# aansluitschema.net
KiCad netlist of a schematic drawn in EAGLE
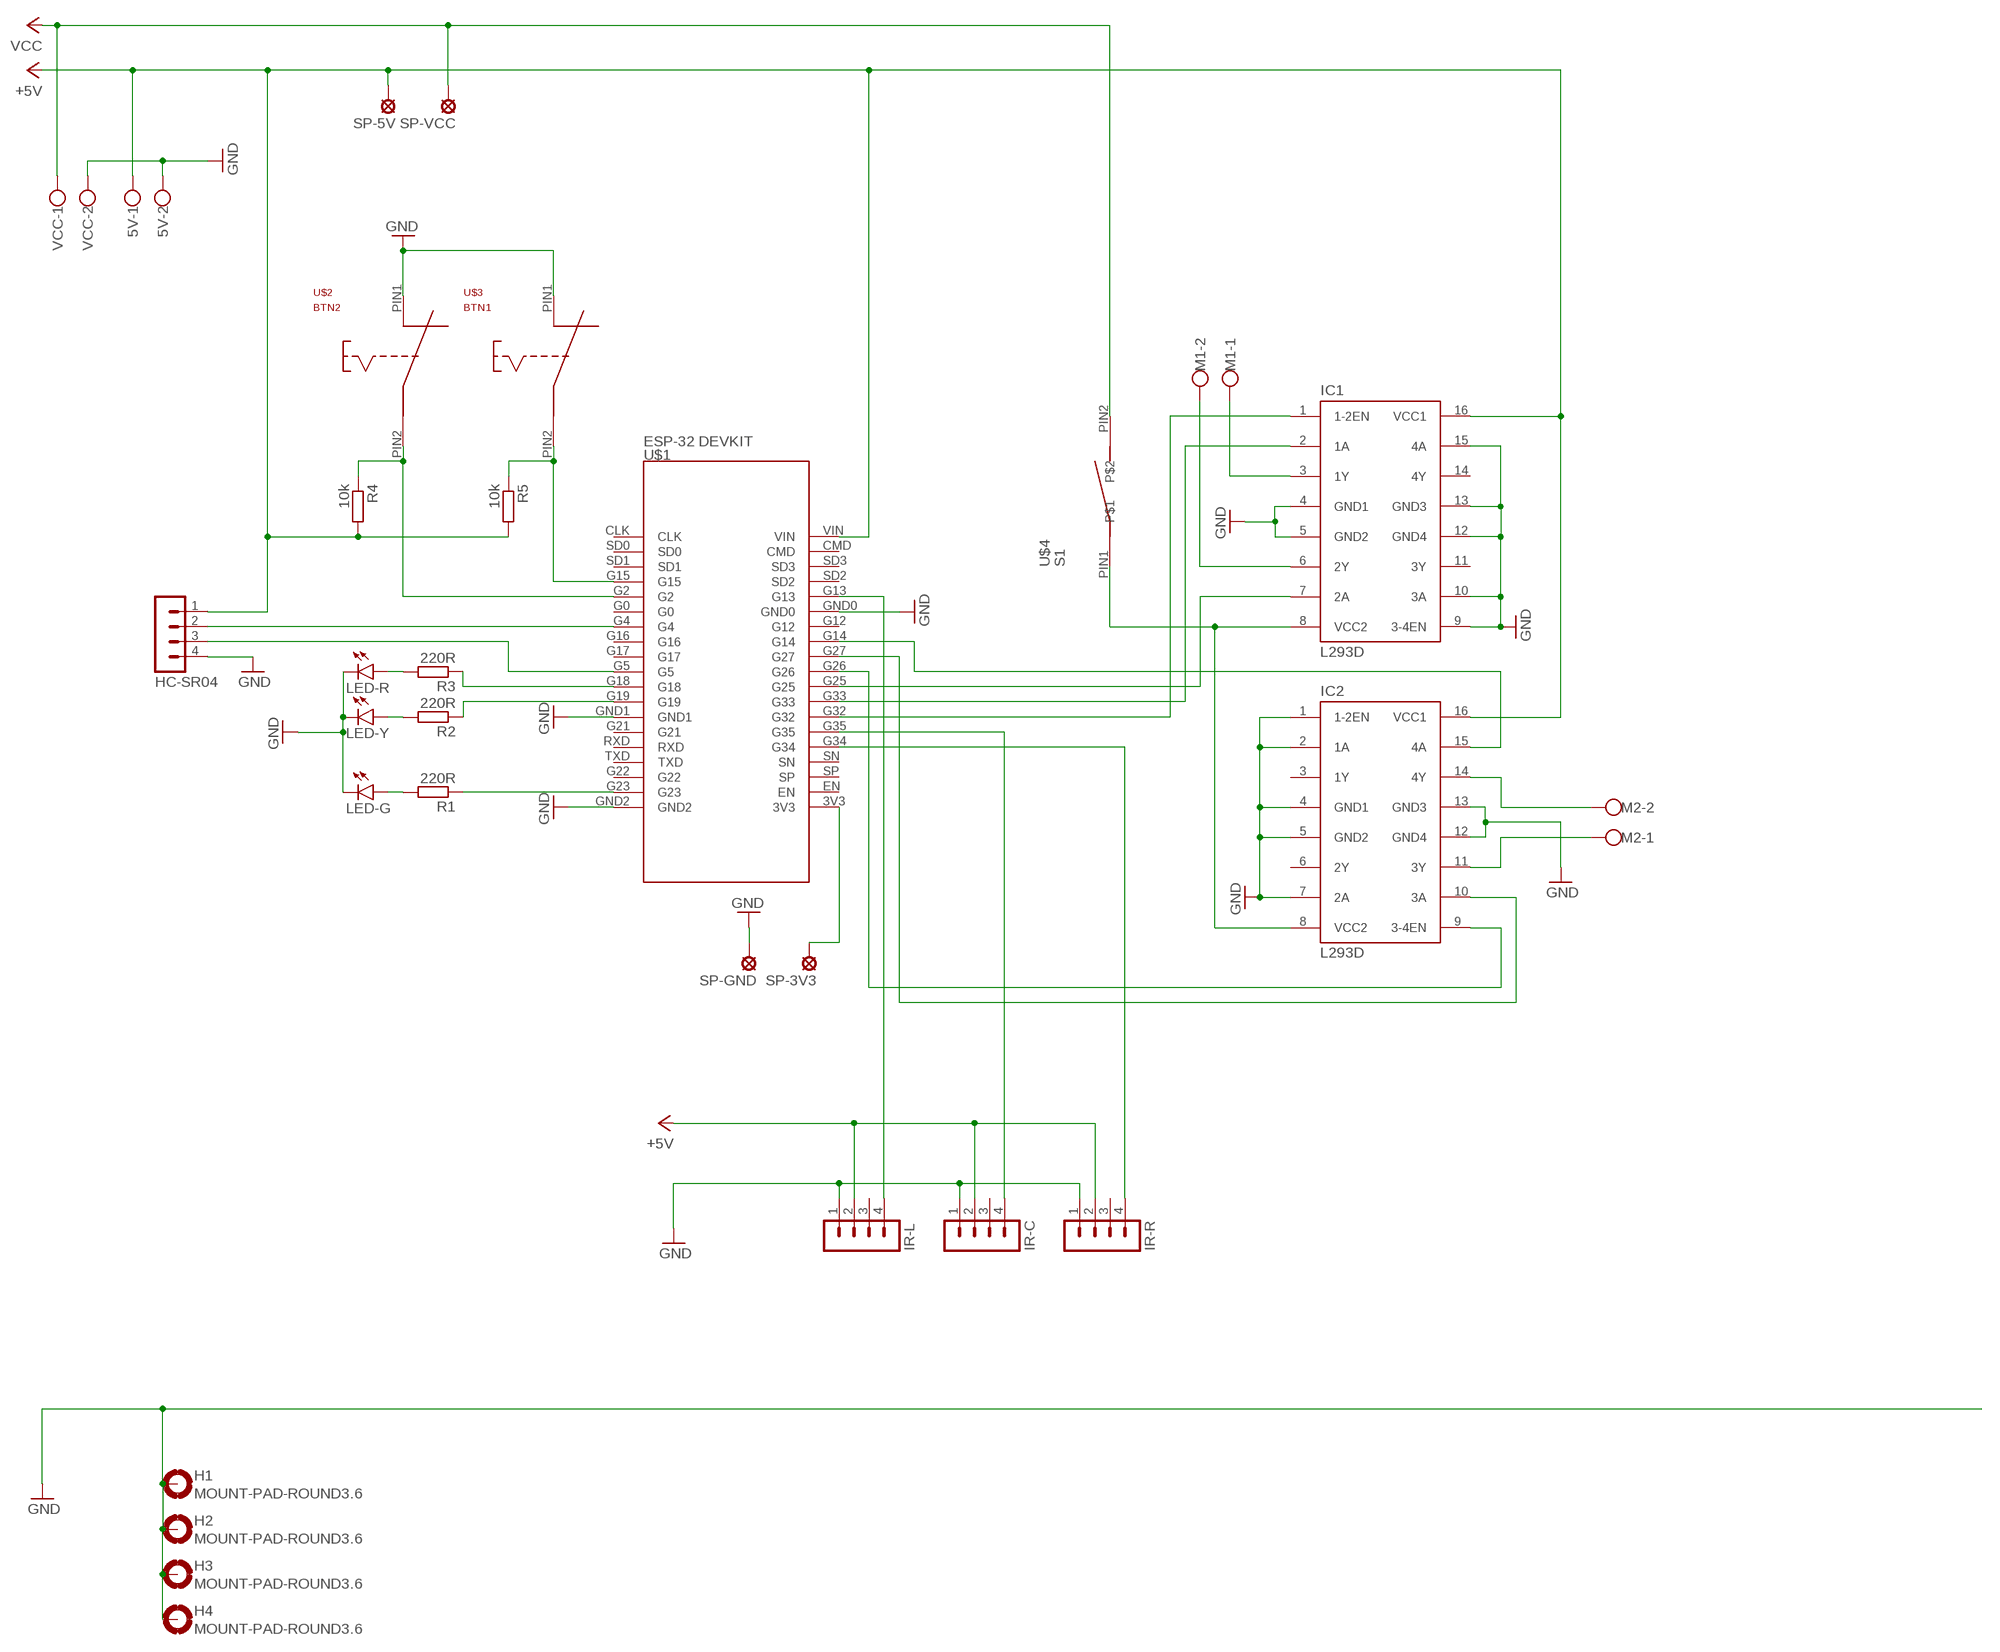
[diagram p0: schematic, sheet 1]

(export (version "E")
  (design (tool "Eeschema 10.0.6"))
  (components
    (comp (ref "5V")
      (value "W237-102")
      (footprint "eagle-import:W237-102")
      (fields (field (name "MPN") "237-102"))
      (libsource (lib "eagle-import") (part "W237-102"))
    )
    (comp (ref "H1")
      (value "MOUNT-PAD-ROUND3.6")
      (footprint "eagle-import:3,6-PAD")
      (libsource (lib "eagle-import") (part "MOUNT-PAD-ROUND3.6"))
    )
    (comp (ref "H2")
      (value "MOUNT-PAD-ROUND3.6")
      (footprint "eagle-import:3,6-PAD")
      (libsource (lib "eagle-import") (part "MOUNT-PAD-ROUND3.6"))
    )
    (comp (ref "H3")
      (value "MOUNT-PAD-ROUND3.6")
      (footprint "eagle-import:3,6-PAD")
      (libsource (lib "eagle-import") (part "MOUNT-PAD-ROUND3.6"))
    )
    (comp (ref "H4")
      (value "MOUNT-PAD-ROUND3.6")
      (footprint "eagle-import:3,6-PAD")
      (libsource (lib "eagle-import") (part "MOUNT-PAD-ROUND3.6"))
    )
    (comp (ref "HC-SR04")
      (value "MA04-1")
      (footprint "eagle-import:MA04-1")
      (libsource (lib "eagle-import") (part "MA04-1"))
    )
    (comp (ref "IC1")
      (value "L293D")
      (footprint "eagle-import:DIL16")
      (fields (field (name "MF") "Arrow Electronics") (field (name "MPN") "L293E"))
      (libsource (lib "eagle-import") (part "L293E"))
    )
    (comp (ref "IC2")
      (value "L293D")
      (footprint "eagle-import:DIL16")
      (fields (field (name "MF") "Arrow Electronics") (field (name "MPN") "L293E"))
      (libsource (lib "eagle-import") (part "L293E"))
    )
    (comp (ref "IR-C")
      (value "MA04-1")
      (footprint "eagle-import:MA04-1")
      (libsource (lib "eagle-import") (part "MA04-1"))
    )
    (comp (ref "IR-L")
      (value "MA04-1")
      (footprint "eagle-import:MA04-1")
      (libsource (lib "eagle-import") (part "MA04-1"))
    )
    (comp (ref "IR-R")
      (value "MA04-1")
      (footprint "eagle-import:MA04-1")
      (libsource (lib "eagle-import") (part "MA04-1"))
    )
    (comp (ref "LED-G")
      (value "LED5MM")
      (footprint "eagle-import:LED5MM")
      (libsource (lib "eagle-import") (part "LED5MM"))
    )
    (comp (ref "LED-R")
      (value "LED5MM")
      (footprint "eagle-import:LED5MM")
      (libsource (lib "eagle-import") (part "LED5MM"))
    )
    (comp (ref "LED-Y")
      (value "LED5MM")
      (footprint "eagle-import:LED5MM")
      (libsource (lib "eagle-import") (part "LED5MM"))
    )
    (comp (ref "M1")
      (value "W237-102")
      (footprint "eagle-import:W237-102")
      (fields (field (name "MPN") "237-102"))
      (libsource (lib "eagle-import") (part "W237-102"))
    )
    (comp (ref "M2")
      (value "W237-102")
      (footprint "eagle-import:W237-102")
      (fields (field (name "MPN") "237-102"))
      (libsource (lib "eagle-import") (part "W237-102"))
    )
    (comp (ref "R1")
      (value "220R")
      (footprint "eagle-import:0207_10")
      (libsource (lib "eagle-import") (part "R-EU_0207/10"))
    )
    (comp (ref "R2")
      (value "220R")
      (footprint "eagle-import:0207_10")
      (libsource (lib "eagle-import") (part "R-EU_0207/10"))
    )
    (comp (ref "R3")
      (value "220R")
      (footprint "eagle-import:0207_10")
      (libsource (lib "eagle-import") (part "R-EU_0207/10"))
    )
    (comp (ref "R4")
      (value "10k")
      (footprint "eagle-import:0207_10")
      (libsource (lib "eagle-import") (part "R-EU_0207/10"))
    )
    (comp (ref "R5")
      (value "10k")
      (footprint "eagle-import:0207_10")
      (libsource (lib "eagle-import") (part "R-EU_0207/10"))
    )
    (comp (ref "SP-3V3")
      (value "LSP10")
      (footprint "eagle-import:LSP10")
      (libsource (lib "eagle-import") (part "LSP10"))
    )
    (comp (ref "SP-5V")
      (value "LSP10")
      (footprint "eagle-import:LSP10")
      (libsource (lib "eagle-import") (part "LSP10"))
    )
    (comp (ref "SP-GND")
      (value "LSP10")
      (footprint "eagle-import:LSP10")
      (libsource (lib "eagle-import") (part "LSP10"))
    )
    (comp (ref "SP-VCC")
      (value "LSP10")
      (footprint "eagle-import:LSP10")
      (libsource (lib "eagle-import") (part "LSP10"))
    )
    (comp (ref "U$1")
      (value "ESP-32 DEVKIT")
      (footprint "eagle-import:ESP-32_DEVKIT")
      (libsource (lib "eagle-import") (part "ESP-32_DEVKIT"))
    )
    (comp (ref "U$2")
      (value "BTN2")
      (footprint "eagle-import:PUSHBUTTON")
      (libsource (lib "eagle-import") (part "PUSHBUTTON"))
    )
    (comp (ref "U$3")
      (value "BTN1")
      (footprint "eagle-import:PUSHBUTTON")
      (libsource (lib "eagle-import") (part "PUSHBUTTON"))
    )
    (comp (ref "U$4")
      (value "S1")
      (footprint "eagle-import:SWITCH")
      (libsource (lib "eagle-import") (part "SWITCH"))
    )
    (comp (ref "VCC")
      (value "W237-102")
      (footprint "eagle-import:W237-102")
      (fields (field (name "MPN") "237-102"))
      (libsource (lib "eagle-import") (part "W237-102"))
    )
  )
  (nets
    (net (code "1") (name "+5V") (class "Default")
      (node (ref "5V") (pin "1") (pinfunction "KL_1") (pintype "passive"))
      (node (ref "HC-SR04") (pin "1") (pinfunction "1_1") (pintype "passive"))
      (node (ref "IC1") (pin "16") (pinfunction "VCC1_16") (pintype "power_in"))
      (node (ref "IC2") (pin "16") (pinfunction "VCC1_16") (pintype "power_in"))
      (node (ref "IR-C") (pin "2") (pinfunction "2_2") (pintype "passive"))
      (node (ref "IR-L") (pin "2") (pinfunction "2_2") (pintype "passive"))
      (node (ref "IR-R") (pin "2") (pinfunction "2_2") (pintype "passive"))
      (node (ref "R4") (pin "2") (pinfunction "2_2") (pintype "passive"))
      (node (ref "R5") (pin "2") (pinfunction "2_2") (pintype "passive"))
      (node (ref "SP-5V") (pin "MP") (pinfunction "MP_MP") (pintype "passive"))
      (node (ref "U$1") (pin "VIN") (pinfunction "VIN_VIN") (pintype "power_in"))
    )
    (net (code "2") (name "GND") (class "Default")
      (node (ref "5V") (pin "2") (pinfunction "KL_2") (pintype "passive"))
      (node (ref "H1") (pin "B3,6") (pinfunction "MOUNT_B3,6") (pintype "passive"))
      (node (ref "H2") (pin "B3,6") (pinfunction "MOUNT_B3,6") (pintype "passive"))
      (node (ref "H3") (pin "B3,6") (pinfunction "MOUNT_B3,6") (pintype "passive"))
      (node (ref "H4") (pin "B3,6") (pinfunction "MOUNT_B3,6") (pintype "passive"))
      (node (ref "HC-SR04") (pin "4") (pinfunction "4_4") (pintype "passive"))
      (node (ref "IC1") (pin "10") (pinfunction "3A_10") (pintype "input"))
      (node (ref "IC1") (pin "12") (pinfunction "GND4_12") (pintype "power_in"))
      (node (ref "IC1") (pin "13") (pinfunction "GND3_13") (pintype "power_in"))
      (node (ref "IC1") (pin "15") (pinfunction "4A_15") (pintype "input"))
      (node (ref "IC1") (pin "4") (pinfunction "GND1_4") (pintype "power_in"))
      (node (ref "IC1") (pin "5") (pinfunction "GND2_5") (pintype "power_in"))
      (node (ref "IC1") (pin "9") (pinfunction "3-4EN_9") (pintype "input"))
      (node (ref "IC2") (pin "1") (pinfunction "1-2EN_1") (pintype "input"))
      (node (ref "IC2") (pin "12") (pinfunction "GND4_12") (pintype "power_in"))
      (node (ref "IC2") (pin "13") (pinfunction "GND3_13") (pintype "power_in"))
      (node (ref "IC2") (pin "2") (pinfunction "1A_2") (pintype "input"))
      (node (ref "IC2") (pin "4") (pinfunction "GND1_4") (pintype "power_in"))
      (node (ref "IC2") (pin "5") (pinfunction "GND2_5") (pintype "power_in"))
      (node (ref "IC2") (pin "7") (pinfunction "2A_7") (pintype "input"))
      (node (ref "IR-C") (pin "1") (pinfunction "1_1") (pintype "passive"))
      (node (ref "IR-L") (pin "1") (pinfunction "1_1") (pintype "passive"))
      (node (ref "IR-R") (pin "1") (pinfunction "1_1") (pintype "passive"))
      (node (ref "LED-G") (pin "K") (pinfunction "C_K") (pintype "passive"))
      (node (ref "LED-R") (pin "K") (pinfunction "C_K") (pintype "passive"))
      (node (ref "LED-Y") (pin "K") (pinfunction "C_K") (pintype "passive"))
      (node (ref "SP-GND") (pin "MP") (pinfunction "MP_MP") (pintype "passive"))
      (node (ref "U$1") (pin "GND0") (pinfunction "GND0_GND0") (pintype "power_in"))
      (node (ref "U$1") (pin "GND1") (pinfunction "GND1_GND1") (pintype "power_in"))
      (node (ref "U$1") (pin "GND2") (pinfunction "GND2_GND2") (pintype "power_in"))
      (node (ref "U$2") (pin "PIN1") (pinfunction "PIN1_PIN1") (pintype "bidirectional"))
      (node (ref "U$3") (pin "PIN1") (pinfunction "PIN1_PIN1") (pintype "bidirectional"))
      (node (ref "VCC") (pin "2") (pinfunction "KL_2") (pintype "passive"))
    )
    (net (code "3") (name "Net-(HC-SR04-Pad2)") (class "Default")
      (node (ref "HC-SR04") (pin "2") (pinfunction "2_2") (pintype "passive"))
      (node (ref "U$1") (pin "G4") (pinfunction "G4_G4") (pintype "bidirectional"))
    )
    (net (code "4") (name "Net-(HC-SR04-Pad3)") (class "Default")
      (node (ref "HC-SR04") (pin "3") (pinfunction "3_3") (pintype "passive"))
      (node (ref "U$1") (pin "G5") (pinfunction "G5_G5") (pintype "bidirectional"))
    )
    (net (code "5") (name "Net-(IC1-1-2EN)") (class "Default")
      (node (ref "IC1") (pin "1") (pinfunction "1-2EN_1") (pintype "input"))
      (node (ref "U$1") (pin "G32") (pinfunction "G32_G32") (pintype "bidirectional"))
    )
    (net (code "6") (name "Net-(IC1-1A)") (class "Default")
      (node (ref "IC1") (pin "2") (pinfunction "1A_2") (pintype "input"))
      (node (ref "U$1") (pin "G33") (pinfunction "G33_G33") (pintype "bidirectional"))
    )
    (net (code "7") (name "Net-(IC1-1Y)") (class "Default")
      (node (ref "IC1") (pin "3") (pinfunction "1Y_3") (pintype "output"))
      (node (ref "M1") (pin "1") (pinfunction "KL_1") (pintype "passive"))
    )
    (net (code "8") (name "Net-(IC1-2A)") (class "Default")
      (node (ref "IC1") (pin "7") (pinfunction "2A_7") (pintype "input"))
      (node (ref "U$1") (pin "G25") (pinfunction "G25_G25") (pintype "bidirectional"))
    )
    (net (code "9") (name "Net-(IC1-2Y)") (class "Default")
      (node (ref "IC1") (pin "6") (pinfunction "2Y_6") (pintype "output"))
      (node (ref "M1") (pin "2") (pinfunction "KL_2") (pintype "passive"))
    )
    (net (code "10") (name "Net-(IC1-VCC2)") (class "Default")
      (node (ref "IC1") (pin "8") (pinfunction "VCC2_8") (pintype "power_in"))
      (node (ref "IC2") (pin "8") (pinfunction "VCC2_8") (pintype "power_in"))
      (node (ref "U$4") (pin "PIN1") (pinfunction "P$1_PIN1") (pintype "bidirectional"))
    )
    (net (code "11") (name "Net-(IC2-3-4EN)") (class "Default")
      (node (ref "IC2") (pin "9") (pinfunction "3-4EN_9") (pintype "input"))
      (node (ref "U$1") (pin "G26") (pinfunction "G26_G26") (pintype "bidirectional"))
    )
    (net (code "12") (name "Net-(IC2-3A)") (class "Default")
      (node (ref "IC2") (pin "10") (pinfunction "3A_10") (pintype "input"))
      (node (ref "U$1") (pin "G27") (pinfunction "G27_G27") (pintype "bidirectional"))
    )
    (net (code "13") (name "Net-(IC2-3Y)") (class "Default")
      (node (ref "IC2") (pin "11") (pinfunction "3Y_11") (pintype "output"))
      (node (ref "M2") (pin "1") (pinfunction "KL_1") (pintype "passive"))
    )
    (net (code "14") (name "Net-(IC2-4A)") (class "Default")
      (node (ref "IC2") (pin "15") (pinfunction "4A_15") (pintype "input"))
      (node (ref "U$1") (pin "G14") (pinfunction "G14_G14") (pintype "bidirectional"))
    )
    (net (code "15") (name "Net-(IC2-4Y)") (class "Default")
      (node (ref "IC2") (pin "14") (pinfunction "4Y_14") (pintype "output"))
      (node (ref "M2") (pin "2") (pinfunction "KL_2") (pintype "passive"))
    )
    (net (code "16") (name "Net-(IR-C-Pad4)") (class "Default")
      (node (ref "IR-C") (pin "4") (pinfunction "4_4") (pintype "passive"))
      (node (ref "U$1") (pin "G35") (pinfunction "G35_G35") (pintype "bidirectional"))
    )
    (net (code "17") (name "Net-(IR-L-Pad4)") (class "Default")
      (node (ref "IR-L") (pin "4") (pinfunction "4_4") (pintype "passive"))
      (node (ref "U$1") (pin "G13") (pinfunction "G13_G13") (pintype "bidirectional"))
    )
    (net (code "18") (name "Net-(IR-R-Pad4)") (class "Default")
      (node (ref "IR-R") (pin "4") (pinfunction "4_4") (pintype "passive"))
      (node (ref "U$1") (pin "G34") (pinfunction "G34_G34") (pintype "bidirectional"))
    )
    (net (code "19") (name "Net-(LED-G-PadA)") (class "Default")
      (node (ref "LED-G") (pin "A") (pinfunction "A_A") (pintype "passive"))
      (node (ref "R1") (pin "2") (pinfunction "2_2") (pintype "passive"))
    )
    (net (code "20") (name "Net-(LED-R-PadA)") (class "Default")
      (node (ref "LED-R") (pin "A") (pinfunction "A_A") (pintype "passive"))
      (node (ref "R3") (pin "2") (pinfunction "2_2") (pintype "passive"))
    )
    (net (code "21") (name "Net-(LED-Y-PadA)") (class "Default")
      (node (ref "LED-Y") (pin "A") (pinfunction "A_A") (pintype "passive"))
      (node (ref "R2") (pin "2") (pinfunction "2_2") (pintype "passive"))
    )
    (net (code "22") (name "Net-(R1-Pad1)") (class "Default")
      (node (ref "R1") (pin "1") (pinfunction "1_1") (pintype "passive"))
      (node (ref "U$1") (pin "G23") (pinfunction "G23_G23") (pintype "bidirectional"))
    )
    (net (code "23") (name "Net-(R2-Pad1)") (class "Default")
      (node (ref "R2") (pin "1") (pinfunction "1_1") (pintype "passive"))
      (node (ref "U$1") (pin "G19") (pinfunction "G19_G19") (pintype "bidirectional"))
    )
    (net (code "24") (name "Net-(R3-Pad1)") (class "Default")
      (node (ref "R3") (pin "1") (pinfunction "1_1") (pintype "passive"))
      (node (ref "U$1") (pin "G18") (pinfunction "G18_G18") (pintype "bidirectional"))
    )
    (net (code "25") (name "Net-(R4-Pad1)") (class "Default")
      (node (ref "R4") (pin "1") (pinfunction "1_1") (pintype "passive"))
      (node (ref "U$1") (pin "G2") (pinfunction "G2_G2") (pintype "bidirectional"))
      (node (ref "U$2") (pin "PIN2") (pinfunction "PIN2_PIN2") (pintype "bidirectional"))
    )
    (net (code "26") (name "Net-(R5-Pad1)") (class "Default")
      (node (ref "R5") (pin "1") (pinfunction "1_1") (pintype "passive"))
      (node (ref "U$1") (pin "G15") (pinfunction "G15_G15") (pintype "bidirectional"))
      (node (ref "U$3") (pin "PIN2") (pinfunction "PIN2_PIN2") (pintype "bidirectional"))
    )
    (net (code "27") (name "Net-(SP-3V3-PadMP)") (class "Default")
      (node (ref "SP-3V3") (pin "MP") (pinfunction "MP_MP") (pintype "passive"))
      (node (ref "U$1") (pin "3V3") (pinfunction "3V3_3V3") (pintype "power_in"))
    )
    (net (code "28") (name "VCC") (class "Default")
      (node (ref "SP-VCC") (pin "MP") (pinfunction "MP_MP") (pintype "passive"))
      (node (ref "U$4") (pin "PIN2") (pinfunction "P$2_PIN2") (pintype "bidirectional"))
      (node (ref "VCC") (pin "1") (pinfunction "KL_1") (pintype "passive"))
    )
    (net (code "29") (name "unconnected-(IC1-3Y-Pad11)") (class "Default")
      (node (ref "IC1") (pin "11") (pinfunction "3Y_11") (pintype "output"))
    )
    (net (code "30") (name "unconnected-(IC1-4Y-Pad14)") (class "Default")
      (node (ref "IC1") (pin "14") (pinfunction "4Y_14") (pintype "output"))
    )
    (net (code "31") (name "unconnected-(IC2-1Y-Pad3)") (class "Default")
      (node (ref "IC2") (pin "3") (pinfunction "1Y_3") (pintype "output"))
    )
    (net (code "32") (name "unconnected-(IC2-2Y-Pad6)") (class "Default")
      (node (ref "IC2") (pin "6") (pinfunction "2Y_6") (pintype "output"))
    )
    (net (code "33") (name "unconnected-(IR-C-Pad3)") (class "Default")
      (node (ref "IR-C") (pin "3") (pinfunction "3_3") (pintype "passive"))
    )
    (net (code "34") (name "unconnected-(IR-L-Pad3)") (class "Default")
      (node (ref "IR-L") (pin "3") (pinfunction "3_3") (pintype "passive"))
    )
    (net (code "35") (name "unconnected-(IR-R-Pad3)") (class "Default")
      (node (ref "IR-R") (pin "3") (pinfunction "3_3") (pintype "passive"))
    )
    (net (code "36") (name "unconnected-(U$1-PadCLK)") (class "Default")
      (node (ref "U$1") (pin "CLK") (pinfunction "CLK_CLK") (pintype "bidirectional"))
    )
    (net (code "37") (name "unconnected-(U$1-PadCMD)") (class "Default")
      (node (ref "U$1") (pin "CMD") (pinfunction "CMD_CMD") (pintype "bidirectional"))
    )
    (net (code "38") (name "unconnected-(U$1-PadEN)") (class "Default")
      (node (ref "U$1") (pin "EN") (pinfunction "EN_EN") (pintype "bidirectional"))
    )
    (net (code "39") (name "unconnected-(U$1-PadG0)") (class "Default")
      (node (ref "U$1") (pin "G0") (pinfunction "G0_G0") (pintype "bidirectional"))
    )
    (net (code "40") (name "unconnected-(U$1-PadG12)") (class "Default")
      (node (ref "U$1") (pin "G12") (pinfunction "G12_G12") (pintype "bidirectional"))
    )
    (net (code "41") (name "unconnected-(U$1-PadG16)") (class "Default")
      (node (ref "U$1") (pin "G16") (pinfunction "G16_G16") (pintype "bidirectional"))
    )
    (net (code "42") (name "unconnected-(U$1-PadG17)") (class "Default")
      (node (ref "U$1") (pin "G17") (pinfunction "G17_G17") (pintype "bidirectional"))
    )
    (net (code "43") (name "unconnected-(U$1-PadG21)") (class "Default")
      (node (ref "U$1") (pin "G21") (pinfunction "G21_G21") (pintype "bidirectional"))
    )
    (net (code "44") (name "unconnected-(U$1-PadG22)") (class "Default")
      (node (ref "U$1") (pin "G22") (pinfunction "G22_G22") (pintype "bidirectional"))
    )
    (net (code "45") (name "unconnected-(U$1-PadRXD)") (class "Default")
      (node (ref "U$1") (pin "RXD") (pinfunction "RXD_RXD") (pintype "bidirectional"))
    )
    (net (code "46") (name "unconnected-(U$1-PadSD0)") (class "Default")
      (node (ref "U$1") (pin "SD0") (pinfunction "SD0_SD0") (pintype "bidirectional"))
    )
    (net (code "47") (name "unconnected-(U$1-PadSD1)") (class "Default")
      (node (ref "U$1") (pin "SD1") (pinfunction "SD1_SD1") (pintype "bidirectional"))
    )
    (net (code "48") (name "unconnected-(U$1-PadSD2)") (class "Default")
      (node (ref "U$1") (pin "SD2") (pinfunction "SD2_SD2") (pintype "bidirectional"))
    )
    (net (code "49") (name "unconnected-(U$1-PadSD3)") (class "Default")
      (node (ref "U$1") (pin "SD3") (pinfunction "SD3_SD3") (pintype "bidirectional"))
    )
    (net (code "50") (name "unconnected-(U$1-PadSN)") (class "Default")
      (node (ref "U$1") (pin "SN") (pinfunction "SN_SN") (pintype "bidirectional"))
    )
    (net (code "51") (name "unconnected-(U$1-PadSP)") (class "Default")
      (node (ref "U$1") (pin "SP") (pinfunction "SP_SP") (pintype "bidirectional"))
    )
    (net (code "52") (name "unconnected-(U$1-PadTXD)") (class "Default")
      (node (ref "U$1") (pin "TXD") (pinfunction "TXD_TXD") (pintype "bidirectional"))
    )
  )
)
